# untitled.net
KiCad netlist of a schematic drawn in EAGLE
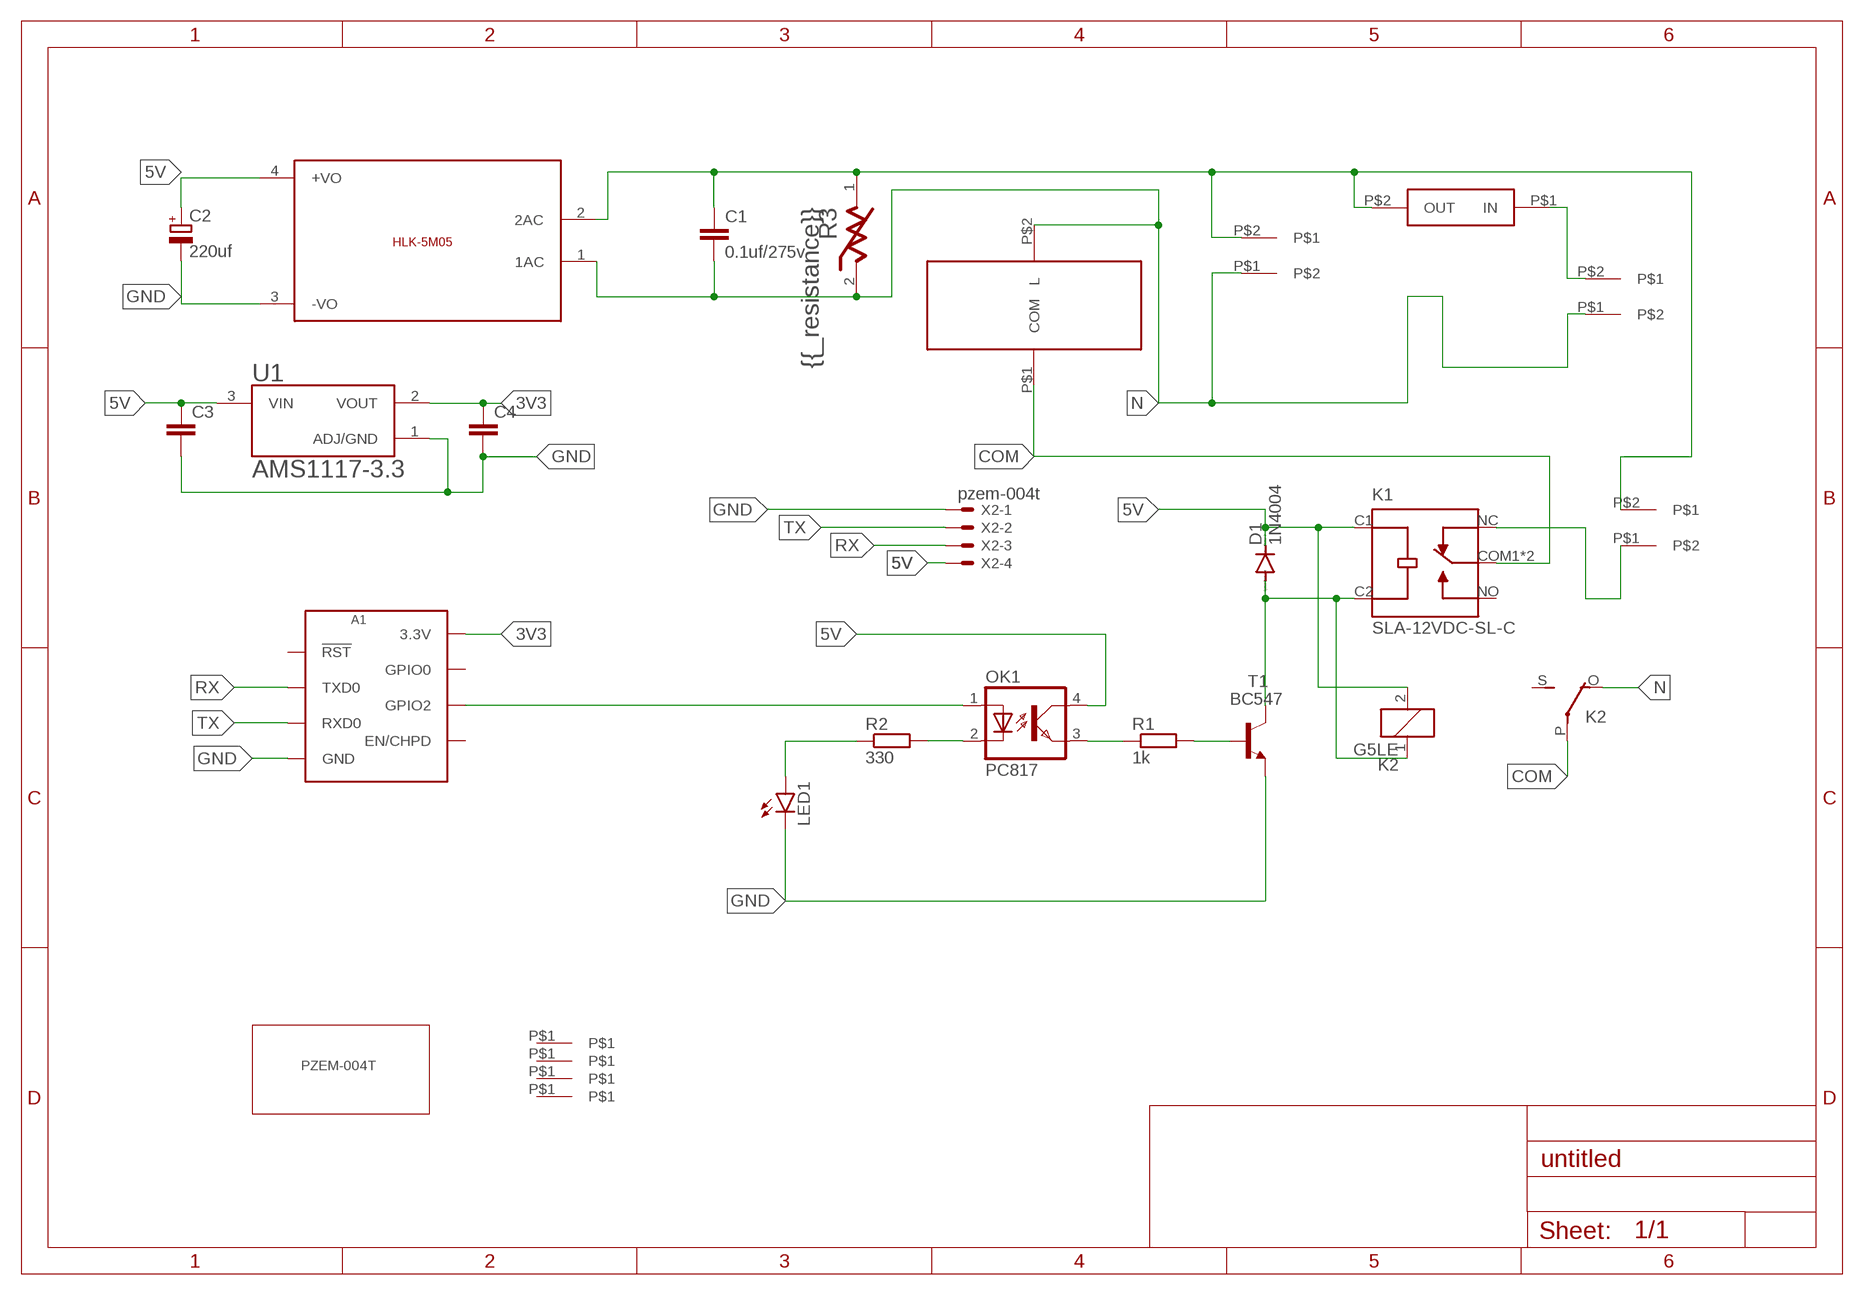
[diagram p0: schematic, sheet 1]

(export (version "E")
  (design (tool "Eeschema 10.0.6"))
  (components
    (comp (ref "220")
      (value "KF76")
      (footprint "eagle-import:KF76")
      (libsource (lib "eagle-import") (part "KF76"))
    )
    (comp (ref "A1")
      (value "ESP8266_ESP-01")
      (footprint "eagle-import:ESP8266_ESP-01_NO-SILKSCREEN")
      (libsource (lib "eagle-import") (part "ESP8266_ESP-?01"))
    )
    (comp (ref "C1")
      (value "0.1uf/275v")
      (footprint "eagle-import:C7.5B5")
      (libsource (lib "eagle-import") (part "C7.5/5"))
    )
    (comp (ref "C2")
      (value "220uf")
      (footprint "eagle-import:E2-5")
      (libsource (lib "eagle-import") (part "CPOL-EUE2-5"))
    )
    (comp (ref "C3")
      (value "C-EUC0805")
      (footprint "eagle-import:C0805")
      (libsource (lib "eagle-import") (part "C-EUC0805"))
    )
    (comp (ref "C4")
      (value "C-EUC0805")
      (footprint "eagle-import:C0805")
      (libsource (lib "eagle-import") (part "C-EUC0805"))
    )
    (comp (ref "D1")
      (value "1N4004")
      (footprint "eagle-import:DO41-10")
      (libsource (lib "eagle-import") (part "1N4004"))
    )
    (comp (ref "K1")
      (value "SLA-12VDC-SL-C")
      (footprint "eagle-import:RELAY_SLA-12VDC-SL-C")
      (fields (field (name "MF") "Songle Relay"))
      (libsource (lib "eagle-import") (part "SLA-12VDC-SL-C"))
    )
    (comp (ref "K2")
      (value "G5LE")
      (footprint "eagle-import:G5LE")
      (libsource (lib "eagle-import") (part "G5LE"))
    )
    (comp (ref "LED1")
      (value "LED5MM")
      (footprint "eagle-import:LED5MM")
      (libsource (lib "eagle-import") (part "LED5MM"))
    )
    (comp (ref "OK1")
      (value "PC817")
      (footprint "eagle-import:DIL04")
      (fields (field (name "MPN") "PC817X4J000F"))
      (libsource (lib "eagle-import") (part "PC817"))
    )
    (comp (ref "PZEM")
      (value "KF76")
      (footprint "eagle-import:KF76")
      (libsource (lib "eagle-import") (part "KF76"))
    )
    (comp (ref "R1")
      (value "1k")
      (footprint "eagle-import:0207_15")
      (libsource (lib "eagle-import") (part "R-EU_0207/15"))
    )
    (comp (ref "R2")
      (value "330")
      (footprint "eagle-import:0207_15")
      (libsource (lib "eagle-import") (part "R-EU_0207/15"))
    )
    (comp (ref "R3")
      (value "10D561K")
      (footprint "eagle-import:BOURNS_INC_MOV-10D471K_0")
      (fields
        (field (name "DIGIKEY_PART_NUMBER") "MOV-10D471K-ND")
        (field (name "MF") "Bourns Inc.")
        (field (name "MOUSER_PART_NUMBER") "652-MOV-10D471K")
      )
      (libsource (lib "eagle-import") (part "BOURNS_INC_MOV-10D471KBOURNS_INC_MOV-10D471K_0_0"))
    )
    (comp (ref "RELAY")
      (value "KF76")
      (footprint "eagle-import:KF76")
      (libsource (lib "eagle-import") (part "KF76"))
    )
    (comp (ref "T1")
      (value "BC547")
      (footprint "eagle-import:TO92")
      (libsource (lib "eagle-import") (part "BC547"))
    )
    (comp (ref "U$1")
      (value "5VDC/5W")
      (footprint "eagle-import:HLK-5M05")
      (libsource (lib "eagle-import") (part "HLK-5M05"))
    )
    (comp (ref "U$2")
      (value "TOROID")
      (footprint "eagle-import:TOROID")
      (libsource (lib "eagle-import") (part "TOROID"))
    )
    (comp (ref "U$3")
      (value "PZEM")
      (footprint "eagle-import:PZEM_FOOTPRINT")
      (libsource (lib "eagle-import") (part "PZEM"))
    )
    (comp (ref "U$4")
      (value "SAPCER")
      (footprint "eagle-import:SPACER")
      (libsource (lib "eagle-import") (part "SAPCER"))
    )
    (comp (ref "U$5")
      (value "SAPCER")
      (footprint "eagle-import:SPACER")
      (libsource (lib "eagle-import") (part "SAPCER"))
    )
    (comp (ref "U$6")
      (value "SAPCER")
      (footprint "eagle-import:SPACER")
      (libsource (lib "eagle-import") (part "SAPCER"))
    )
    (comp (ref "U$7")
      (value "SAPCER")
      (footprint "eagle-import:SPACER")
      (libsource (lib "eagle-import") (part "SAPCER"))
    )
    (comp (ref "U$8")
      (value "FUSE")
      (footprint "eagle-import:FUSE")
      (libsource (lib "eagle-import") (part "FUSE"))
    )
    (comp (ref "U1")
      (value "AMS1117-3.3")
      (footprint "eagle-import:SOT229P700X180-4N")
      (fields (field (name "MF") "Advanced Monolithic Systems"))
      (libsource (lib "eagle-import") (part "AMS1117-3.3"))
    )
    (comp (ref "X2")
      (value "pzem-004t")
      (footprint "eagle-import:22-23-2041")
      (fields (field (name "MF") "MOLEX") (field (name "MPN") "22-23-2041"))
      (libsource (lib "eagle-import") (part "22-23-2041"))
    )
  )
  (nets
    (net (code "1") (name "3V3") (class "Default")
      (node (ref "A1") (pin "3V3") (pinfunction "3.3V_3V3") (pintype "passive"))
      (node (ref "C4") (pin "1") (pinfunction "1_1") (pintype "passive"))
      (node (ref "U1") (pin "2") (pinfunction "VOUT_2") (pintype "output"))
    )
    (net (code "2") (name "5V") (class "Default")
      (node (ref "C2") (pin "+") (pinfunction "+_+") (pintype "passive"))
      (node (ref "C3") (pin "1") (pinfunction "1_1") (pintype "passive"))
      (node (ref "D1") (pin "C") (pinfunction "C_C") (pintype "passive"))
      (node (ref "K1") (pin "C1") (pinfunction "COIL1_C1") (pintype "passive"))
      (node (ref "K2") (pin "2") (pinfunction "2_2") (pintype "passive"))
      (node (ref "OK1") (pin "4") (pinfunction "COL_4") (pintype "passive"))
      (node (ref "U$1") (pin "4") (pinfunction "+VO_4") (pintype "bidirectional"))
      (node (ref "U1") (pin "3") (pinfunction "VIN_3") (pintype "input"))
      (node (ref "X2") (pin "4") (pinfunction "S_4") (pintype "passive"))
    )
    (net (code "3") (name "COM") (class "Default")
      (node (ref "K1") (pin "COM1") (pinfunction "COM_COM1") (pintype "passive"))
      (node (ref "K1") (pin "COM2") (pinfunction "COM_COM2") (pintype "passive"))
      (node (ref "K2") (pin "P") (pinfunction "P_P") (pintype "passive"))
      (node (ref "U$2") (pin "P$1") (pinfunction "COM_P$1") (pintype "bidirectional"))
    )
    (net (code "4") (name "GND") (class "Default")
      (node (ref "A1") (pin "GND") (pinfunction "GND_GND") (pintype "passive"))
      (node (ref "C2") (pin "-") (pinfunction "-_-") (pintype "passive"))
      (node (ref "C3") (pin "2") (pinfunction "2_2") (pintype "passive"))
      (node (ref "C4") (pin "2") (pinfunction "2_2") (pintype "passive"))
      (node (ref "LED1") (pin "K") (pinfunction "C_K") (pintype "passive"))
      (node (ref "T1") (pin "1") (pinfunction "E_1") (pintype "passive"))
      (node (ref "U$1") (pin "3") (pinfunction "-VO_3") (pintype "bidirectional"))
      (node (ref "U1") (pin "1") (pinfunction "ADJ/GND_1") (pintype "power_in"))
      (node (ref "X2") (pin "1") (pinfunction "S_1") (pintype "passive"))
    )
    (net (code "5") (name "N") (class "Default")
      (node (ref "220") (pin "P$1") (pinfunction "P$2_P$1") (pintype "bidirectional"))
      (node (ref "C1") (pin "2") (pinfunction "2_2") (pintype "passive"))
      (node (ref "K2") (pin "O") (pinfunction "O_O") (pintype "passive"))
      (node (ref "PZEM") (pin "P$1") (pinfunction "P$2_P$1") (pintype "bidirectional"))
      (node (ref "R3") (pin "2") (pinfunction "2_2") (pintype "passive"))
      (node (ref "U$1") (pin "1") (pinfunction "1AC_1") (pintype "bidirectional"))
      (node (ref "U$2") (pin "P$2") (pinfunction "L_P$2") (pintype "bidirectional"))
    )
    (net (code "6") (name "Net-(220-P$1)") (class "Default")
      (node (ref "220") (pin "P$2") (pinfunction "P$1_P$2") (pintype "bidirectional"))
      (node (ref "U$8") (pin "P$1") (pinfunction "IN_P$1") (pintype "bidirectional"))
    )
    (net (code "7") (name "Net-(K1-COIL2)") (class "Default")
      (node (ref "D1") (pin "A") (pinfunction "A_A") (pintype "passive"))
      (node (ref "K1") (pin "C2") (pinfunction "COIL2_C2") (pintype "passive"))
      (node (ref "K2") (pin "1") (pinfunction "1_1") (pintype "passive"))
      (node (ref "T1") (pin "3") (pinfunction "C_3") (pintype "passive"))
    )
    (net (code "8") (name "Net-(LED1-PadA)") (class "Default")
      (node (ref "LED1") (pin "A") (pinfunction "A_A") (pintype "passive"))
      (node (ref "R2") (pin "1") (pinfunction "1_1") (pintype "passive"))
    )
    (net (code "9") (name "Net-(OK1-A)") (class "Default")
      (node (ref "A1") (pin "GPIO2") (pinfunction "GPIO2_GPIO2") (pintype "bidirectional"))
      (node (ref "OK1") (pin "1") (pinfunction "A_1") (pintype "passive"))
    )
    (net (code "10") (name "Net-(OK1-C)") (class "Default")
      (node (ref "OK1") (pin "2") (pinfunction "C_2") (pintype "passive"))
      (node (ref "R2") (pin "2") (pinfunction "2_2") (pintype "passive"))
    )
    (net (code "11") (name "Net-(OK1-EMIT)") (class "Default")
      (node (ref "OK1") (pin "3") (pinfunction "EMIT_3") (pintype "passive"))
      (node (ref "R1") (pin "1") (pinfunction "1_1") (pintype "passive"))
    )
    (net (code "12") (name "Net-(PZEM-P$1)") (class "Default")
      (node (ref "C1") (pin "1") (pinfunction "1_1") (pintype "passive"))
      (node (ref "PZEM") (pin "P$2") (pinfunction "P$1_P$2") (pintype "bidirectional"))
      (node (ref "R3") (pin "1") (pinfunction "1_1") (pintype "passive"))
      (node (ref "RELAY") (pin "P$2") (pinfunction "P$1_P$2") (pintype "bidirectional"))
      (node (ref "U$1") (pin "2") (pinfunction "2AC_2") (pintype "bidirectional"))
      (node (ref "U$8") (pin "P$2") (pinfunction "OUT_P$2") (pintype "bidirectional"))
    )
    (net (code "13") (name "Net-(RELAY-P$2)") (class "Default")
      (node (ref "K1") (pin "NC") (pinfunction "NC_NC") (pintype "passive"))
      (node (ref "RELAY") (pin "P$1") (pinfunction "P$2_P$1") (pintype "bidirectional"))
    )
    (net (code "14") (name "Net-(T1-B)") (class "Default")
      (node (ref "R1") (pin "2") (pinfunction "2_2") (pintype "passive"))
      (node (ref "T1") (pin "2") (pinfunction "B_2") (pintype "passive"))
    )
    (net (code "15") (name "RX") (class "Default")
      (node (ref "A1") (pin "TX") (pinfunction "TXD0_TX") (pintype "bidirectional"))
      (node (ref "X2") (pin "3") (pinfunction "S_3") (pintype "passive"))
    )
    (net (code "16") (name "TX") (class "Default")
      (node (ref "A1") (pin "RX") (pinfunction "RXD0_RX") (pintype "bidirectional"))
      (node (ref "X2") (pin "2") (pinfunction "S_2") (pintype "passive"))
    )
    (net (code "17") (name "unconnected-(A1-EN{slash}CHPD-PadEN{slash}CH_PD)") (class "Default")
      (node (ref "A1") (pin "EN/CH_PD") (pinfunction "EN/CHPD_EN/CH_PD") (pintype "bidirectional"))
    )
    (net (code "18") (name "unconnected-(A1-PadGPIO0)") (class "Default")
      (node (ref "A1") (pin "GPIO0") (pinfunction "GPIO0_GPIO0") (pintype "bidirectional"))
    )
    (net (code "19") (name "unconnected-(A1-~{RST}-PadRST)") (class "Default")
      (node (ref "A1") (pin "RST") (pinfunction "~{RST}_RST") (pintype "bidirectional"))
    )
    (net (code "20") (name "unconnected-(K1-PadNO)") (class "Default")
      (node (ref "K1") (pin "NO") (pinfunction "NO_NO") (pintype "passive"))
    )
    (net (code "21") (name "unconnected-(K2-PadS)") (class "Default")
      (node (ref "K2") (pin "S") (pinfunction "S_S") (pintype "passive"))
    )
    (net (code "22") (name "unconnected-(U$4-PadP$1)") (class "Default")
      (node (ref "U$4") (pin "P$1") (pinfunction "P$1_P$1") (pintype "bidirectional"))
    )
    (net (code "23") (name "unconnected-(U$5-PadP$1)") (class "Default")
      (node (ref "U$5") (pin "P$1") (pinfunction "P$1_P$1") (pintype "bidirectional"))
    )
    (net (code "24") (name "unconnected-(U$6-PadP$1)") (class "Default")
      (node (ref "U$6") (pin "P$1") (pinfunction "P$1_P$1") (pintype "bidirectional"))
    )
    (net (code "25") (name "unconnected-(U$7-PadP$1)") (class "Default")
      (node (ref "U$7") (pin "P$1") (pinfunction "P$1_P$1") (pintype "bidirectional"))
    )
  )
)
